# FT4232_MINI.net
KiCad netlist of a schematic drawn in Altium Designer
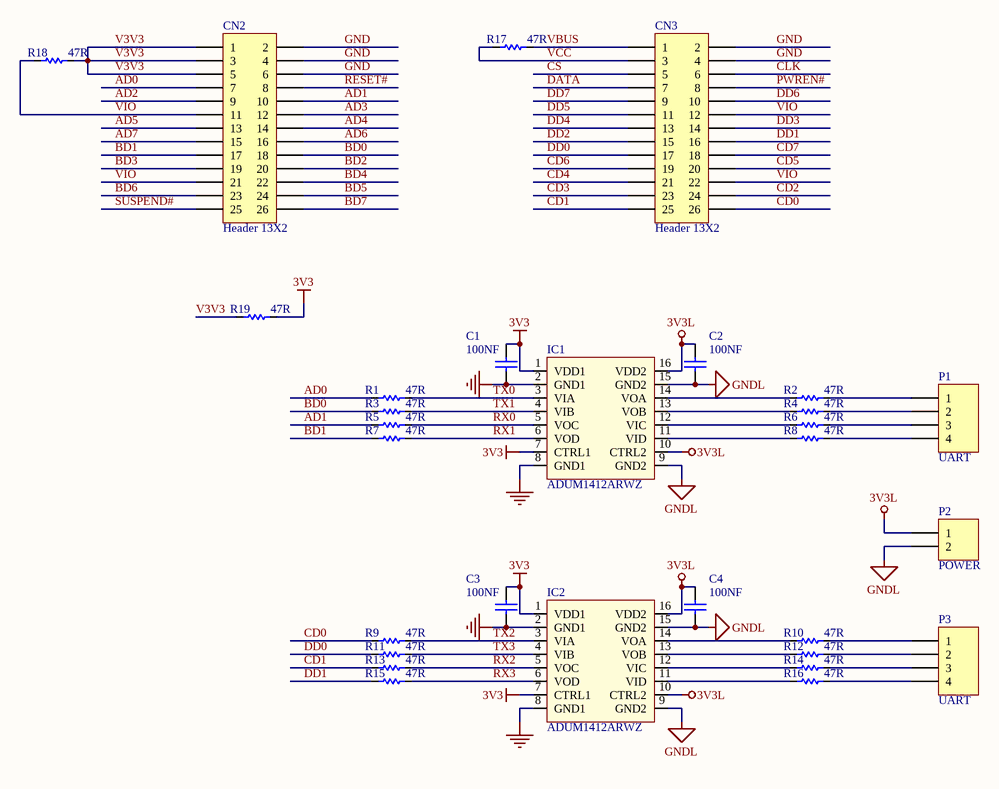
[diagram p0: FT4232_MINI.SchDoc]

(export (version "E")
  (design (tool "Eeschema 10.0.6"))
  (components
    (comp (ref "C1")
      (value "100NF")
      (footprint "CAPC1608X09N")
      (description "CAP CERAMIC 100NF 50VDC 10% SMD 0603   X7R")
      (libsource (lib "VIKO") (part "C_Nonpolar"))
    )
    (comp (ref "C2")
      (value "100NF")
      (footprint "CAPC1608X09N")
      (description "CAP CERAMIC 100NF 50VDC 10% SMD 0603   X7R")
      (libsource (lib "VIKO") (part "C_Nonpolar"))
    )
    (comp (ref "C3")
      (value "100NF")
      (footprint "CAPC1608X09N")
      (description "CAP CERAMIC 100NF 50VDC 10% SMD 0603   X7R")
      (libsource (lib "VIKO") (part "C_Nonpolar"))
    )
    (comp (ref "C4")
      (value "100NF")
      (footprint "CAPC1608X09N")
      (description "CAP CERAMIC 100NF 50VDC 10% SMD 0603   X7R")
      (libsource (lib "VIKO") (part "C_Nonpolar"))
    )
    (comp (ref "CN2")
      (value "Header 13X2")
      (footprint "Pin Header 2x13 TH Pitch 2.54mm")
      (description "Header, 13-Pin, Dual row")
      (fields (field (name "PUBLISHER") "Altium Limited"))
      (libsource (lib "Miscellaneous Connectors") (part "Header 13X2"))
    )
    (comp (ref "CN3")
      (value "Header 13X2")
      (footprint "Pin Header 2x13 TH Pitch 2.54mm")
      (description "Header, 13-Pin, Dual row")
      (fields (field (name "PUBLISHER") "Altium Limited"))
      (libsource (lib "Miscellaneous Connectors") (part "Header 13X2"))
    )
    (comp (ref "IC1")
      (value "ADUM1412ARWZ")
      (footprint "SOIC127P1030X265-16N")
      (description "IC DIGITAL ISOLATOR ADUM1412ARWZ 4 CH SMD SOIC16-W")
      (libsource (lib "VIKO") (part "IC-ADUM1412ARWZ"))
    )
    (comp (ref "IC2")
      (value "ADUM1412ARWZ")
      (footprint "SOIC127P1030X265-16N")
      (description "IC DIGITAL ISOLATOR ADUM1412ARWZ 4 CH SMD SOIC16-W")
      (libsource (lib "VIKO") (part "IC-ADUM1412ARWZ"))
    )
    (comp (ref "P1")
      (value "UART")
      (footprint "Klemens-3.81mm-4H")
      (description "Header, 4-Pin")
      (fields (field (name "PUBLISHER") "Altium Limited"))
      (libsource (lib "Miscellaneous Connectors") (part "Header 4"))
    )
    (comp (ref "P2")
      (value "POWER")
      (footprint "Klemens-3.81mm-2H")
      (description "Header, 2-Pin")
      (fields (field (name "PUBLISHER") "Altium Limited"))
      (libsource (lib "Miscellaneous Connectors") (part "Header 2"))
    )
    (comp (ref "P3")
      (value "UART")
      (footprint "Klemens-3.81mm-4H")
      (description "Header, 4-Pin")
      (fields (field (name "PUBLISHER") "Altium Limited"))
      (libsource (lib "Miscellaneous Connectors") (part "Header 4"))
    )
    (comp (ref "R1")
      (value "47R")
      (footprint "RESC1608X06N")
      (description "RES CARBON 47R 0.1W 1% 100ppm SMD 0603")
      (libsource (lib "VIKO") (part "R"))
    )
    (comp (ref "R2")
      (value "47R")
      (footprint "RESC1608X06N")
      (description "RES CARBON 47R 0.1W 1% 100ppm SMD 0603")
      (libsource (lib "VIKO") (part "R"))
    )
    (comp (ref "R3")
      (value "47R")
      (footprint "RESC1608X06N")
      (description "RES CARBON 47R 0.1W 1% 100ppm SMD 0603")
      (libsource (lib "VIKO") (part "R"))
    )
    (comp (ref "R4")
      (value "47R")
      (footprint "RESC1608X06N")
      (description "RES CARBON 47R 0.1W 1% 100ppm SMD 0603")
      (libsource (lib "VIKO") (part "R"))
    )
    (comp (ref "R5")
      (value "47R")
      (footprint "RESC1608X06N")
      (description "RES CARBON 47R 0.1W 1% 100ppm SMD 0603")
      (libsource (lib "VIKO") (part "R"))
    )
    (comp (ref "R6")
      (value "47R")
      (footprint "RESC1608X06N")
      (description "RES CARBON 47R 0.1W 1% 100ppm SMD 0603")
      (libsource (lib "VIKO") (part "R"))
    )
    (comp (ref "R7")
      (value "47R")
      (footprint "RESC1608X06N")
      (description "RES CARBON 47R 0.1W 1% 100ppm SMD 0603")
      (libsource (lib "VIKO") (part "R"))
    )
    (comp (ref "R8")
      (value "47R")
      (footprint "RESC1608X06N")
      (description "RES CARBON 47R 0.1W 1% 100ppm SMD 0603")
      (libsource (lib "VIKO") (part "R"))
    )
    (comp (ref "R9")
      (value "47R")
      (footprint "RESC1608X06N")
      (description "RES CARBON 47R 0.1W 1% 100ppm SMD 0603")
      (libsource (lib "VIKO") (part "R"))
    )
    (comp (ref "R10")
      (value "47R")
      (footprint "RESC1608X06N")
      (description "RES CARBON 47R 0.1W 1% 100ppm SMD 0603")
      (libsource (lib "VIKO") (part "R"))
    )
    (comp (ref "R11")
      (value "47R")
      (footprint "RESC1608X06N")
      (description "RES CARBON 47R 0.1W 1% 100ppm SMD 0603")
      (libsource (lib "VIKO") (part "R"))
    )
    (comp (ref "R12")
      (value "47R")
      (footprint "RESC1608X06N")
      (description "RES CARBON 47R 0.1W 1% 100ppm SMD 0603")
      (libsource (lib "VIKO") (part "R"))
    )
    (comp (ref "R13")
      (value "47R")
      (footprint "RESC1608X06N")
      (description "RES CARBON 47R 0.1W 1% 100ppm SMD 0603")
      (libsource (lib "VIKO") (part "R"))
    )
    (comp (ref "R14")
      (value "47R")
      (footprint "RESC1608X06N")
      (description "RES CARBON 47R 0.1W 1% 100ppm SMD 0603")
      (libsource (lib "VIKO") (part "R"))
    )
    (comp (ref "R15")
      (value "47R")
      (footprint "RESC1608X06N")
      (description "RES CARBON 47R 0.1W 1% 100ppm SMD 0603")
      (libsource (lib "VIKO") (part "R"))
    )
    (comp (ref "R16")
      (value "47R")
      (footprint "RESC1608X06N")
      (description "RES CARBON 47R 0.1W 1% 100ppm SMD 0603")
      (libsource (lib "VIKO") (part "R"))
    )
    (comp (ref "R17")
      (value "47R")
      (footprint "RESC1608X06N")
      (description "RES CARBON 47R 0.1W 1% 100ppm SMD 0603")
      (libsource (lib "VIKO") (part "R"))
    )
    (comp (ref "R18")
      (value "47R")
      (footprint "RESC1608X06N")
      (description "RES CARBON 47R 0.1W 1% 100ppm SMD 0603")
      (libsource (lib "VIKO") (part "R"))
    )
    (comp (ref "R19")
      (value "47R")
      (footprint "RESC1608X06N")
      (description "RES CARBON 47R 0.1W 1% 100ppm SMD 0603")
      (libsource (lib "VIKO") (part "R"))
    )
  )
  (nets
    (net (code "1") (name "/AD0") (class "Default")
      (node (ref "CN2") (pin "7") (pinfunction "7_7") (pintype "passive"))
      (node (ref "R1") (pin "1") (pinfunction "1_1") (pintype "passive"))
    )
    (net (code "2") (name "/AD1") (class "Default")
      (node (ref "CN2") (pin "10") (pinfunction "10_10") (pintype "passive"))
      (node (ref "R5") (pin "1") (pinfunction "1_1") (pintype "passive"))
    )
    (net (code "3") (name "/AD2") (class "Default")
      (node (ref "CN2") (pin "9") (pinfunction "9_9") (pintype "passive"))
    )
    (net (code "4") (name "/AD3") (class "Default")
      (node (ref "CN2") (pin "12") (pinfunction "12_12") (pintype "passive"))
    )
    (net (code "5") (name "/AD4") (class "Default")
      (node (ref "CN2") (pin "14") (pinfunction "14_14") (pintype "passive"))
    )
    (net (code "6") (name "/AD5") (class "Default")
      (node (ref "CN2") (pin "13") (pinfunction "13_13") (pintype "passive"))
    )
    (net (code "7") (name "/AD6") (class "Default")
      (node (ref "CN2") (pin "16") (pinfunction "16_16") (pintype "passive"))
    )
    (net (code "8") (name "/AD7") (class "Default")
      (node (ref "CN2") (pin "15") (pinfunction "15_15") (pintype "passive"))
    )
    (net (code "9") (name "/BD0") (class "Default")
      (node (ref "CN2") (pin "18") (pinfunction "18_18") (pintype "passive"))
      (node (ref "R3") (pin "1") (pinfunction "1_1") (pintype "passive"))
    )
    (net (code "10") (name "/BD1") (class "Default")
      (node (ref "CN2") (pin "17") (pinfunction "17_17") (pintype "passive"))
      (node (ref "R7") (pin "1") (pinfunction "1_1") (pintype "passive"))
    )
    (net (code "11") (name "/BD2") (class "Default")
      (node (ref "CN2") (pin "20") (pinfunction "20_20") (pintype "passive"))
    )
    (net (code "12") (name "/BD3") (class "Default")
      (node (ref "CN2") (pin "19") (pinfunction "19_19") (pintype "passive"))
    )
    (net (code "13") (name "/BD4") (class "Default")
      (node (ref "CN2") (pin "22") (pinfunction "22_22") (pintype "passive"))
    )
    (net (code "14") (name "/BD5") (class "Default")
      (node (ref "CN2") (pin "24") (pinfunction "24_24") (pintype "passive"))
    )
    (net (code "15") (name "/BD6") (class "Default")
      (node (ref "CN2") (pin "23") (pinfunction "23_23") (pintype "passive"))
    )
    (net (code "16") (name "/BD7") (class "Default")
      (node (ref "CN2") (pin "26") (pinfunction "26_26") (pintype "passive"))
    )
    (net (code "17") (name "/CD0") (class "Default")
      (node (ref "CN3") (pin "26") (pinfunction "26_26") (pintype "passive"))
      (node (ref "R9") (pin "1") (pinfunction "1_1") (pintype "passive"))
    )
    (net (code "18") (name "/CD1") (class "Default")
      (node (ref "CN3") (pin "25") (pinfunction "25_25") (pintype "passive"))
      (node (ref "R13") (pin "1") (pinfunction "1_1") (pintype "passive"))
    )
    (net (code "19") (name "/CD2") (class "Default")
      (node (ref "CN3") (pin "24") (pinfunction "24_24") (pintype "passive"))
    )
    (net (code "20") (name "/CD3") (class "Default")
      (node (ref "CN3") (pin "23") (pinfunction "23_23") (pintype "passive"))
    )
    (net (code "21") (name "/CD4") (class "Default")
      (node (ref "CN3") (pin "21") (pinfunction "21_21") (pintype "passive"))
    )
    (net (code "22") (name "/CD5") (class "Default")
      (node (ref "CN3") (pin "20") (pinfunction "20_20") (pintype "passive"))
    )
    (net (code "23") (name "/CD6") (class "Default")
      (node (ref "CN3") (pin "19") (pinfunction "19_19") (pintype "passive"))
    )
    (net (code "24") (name "/CD7") (class "Default")
      (node (ref "CN3") (pin "18") (pinfunction "18_18") (pintype "passive"))
    )
    (net (code "25") (name "/CLK") (class "Default")
      (node (ref "CN3") (pin "6") (pinfunction "6_6") (pintype "passive"))
    )
    (net (code "26") (name "/CS") (class "Default")
      (node (ref "CN3") (pin "5") (pinfunction "5_5") (pintype "passive"))
    )
    (net (code "27") (name "/DATA") (class "Default")
      (node (ref "CN3") (pin "7") (pinfunction "7_7") (pintype "passive"))
    )
    (net (code "28") (name "/DD0") (class "Default")
      (node (ref "CN3") (pin "17") (pinfunction "17_17") (pintype "passive"))
      (node (ref "R11") (pin "1") (pinfunction "1_1") (pintype "passive"))
    )
    (net (code "29") (name "/DD1") (class "Default")
      (node (ref "CN3") (pin "16") (pinfunction "16_16") (pintype "passive"))
      (node (ref "R15") (pin "1") (pinfunction "1_1") (pintype "passive"))
    )
    (net (code "30") (name "/DD2") (class "Default")
      (node (ref "CN3") (pin "15") (pinfunction "15_15") (pintype "passive"))
    )
    (net (code "31") (name "/DD3") (class "Default")
      (node (ref "CN3") (pin "14") (pinfunction "14_14") (pintype "passive"))
    )
    (net (code "32") (name "/DD4") (class "Default")
      (node (ref "CN3") (pin "13") (pinfunction "13_13") (pintype "passive"))
    )
    (net (code "33") (name "/DD5") (class "Default")
      (node (ref "CN3") (pin "11") (pinfunction "11_11") (pintype "passive"))
    )
    (net (code "34") (name "/DD6") (class "Default")
      (node (ref "CN3") (pin "10") (pinfunction "10_10") (pintype "passive"))
    )
    (net (code "35") (name "/DD7") (class "Default")
      (node (ref "CN3") (pin "9") (pinfunction "9_9") (pintype "passive"))
    )
    (net (code "36") (name "/PWREN#") (class "Default")
      (node (ref "CN3") (pin "8") (pinfunction "8_8") (pintype "passive"))
    )
    (net (code "37") (name "/RESET#") (class "Default")
      (node (ref "CN2") (pin "8") (pinfunction "8_8") (pintype "passive"))
    )
    (net (code "38") (name "/RX0") (class "Default")
      (node (ref "IC1") (pin "5") (pinfunction "VOC_5") (pintype "passive"))
      (node (ref "R5") (pin "2") (pinfunction "2_2") (pintype "passive"))
    )
    (net (code "39") (name "/RX1") (class "Default")
      (node (ref "IC1") (pin "6") (pinfunction "VOD_6") (pintype "passive"))
      (node (ref "R7") (pin "2") (pinfunction "2_2") (pintype "passive"))
    )
    (net (code "40") (name "/RX2") (class "Default")
      (node (ref "IC2") (pin "5") (pinfunction "VOC_5") (pintype "passive"))
      (node (ref "R13") (pin "2") (pinfunction "2_2") (pintype "passive"))
    )
    (net (code "41") (name "/RX3") (class "Default")
      (node (ref "IC2") (pin "6") (pinfunction "VOD_6") (pintype "passive"))
      (node (ref "R15") (pin "2") (pinfunction "2_2") (pintype "passive"))
    )
    (net (code "42") (name "/SUSPEND#") (class "Default")
      (node (ref "CN2") (pin "25") (pinfunction "25_25") (pintype "passive"))
    )
    (net (code "43") (name "/TX0") (class "Default")
      (node (ref "IC1") (pin "3") (pinfunction "VIA_3") (pintype "passive"))
      (node (ref "R1") (pin "2") (pinfunction "2_2") (pintype "passive"))
    )
    (net (code "44") (name "/TX1") (class "Default")
      (node (ref "IC1") (pin "4") (pinfunction "VIB_4") (pintype "passive"))
      (node (ref "R3") (pin "2") (pinfunction "2_2") (pintype "passive"))
    )
    (net (code "45") (name "/TX2") (class "Default")
      (node (ref "IC2") (pin "3") (pinfunction "VIA_3") (pintype "passive"))
      (node (ref "R9") (pin "2") (pinfunction "2_2") (pintype "passive"))
    )
    (net (code "46") (name "/TX3") (class "Default")
      (node (ref "IC2") (pin "4") (pinfunction "VIB_4") (pintype "passive"))
      (node (ref "R11") (pin "2") (pinfunction "2_2") (pintype "passive"))
    )
    (net (code "47") (name "/V3V3") (class "Default")
      (node (ref "CN2") (pin "1") (pinfunction "1_1") (pintype "passive"))
      (node (ref "CN2") (pin "3") (pinfunction "3_3") (pintype "passive"))
      (node (ref "CN2") (pin "5") (pinfunction "5_5") (pintype "passive"))
      (node (ref "R18") (pin "2") (pinfunction "2_2") (pintype "passive"))
      (node (ref "R19") (pin "1") (pinfunction "1_1") (pintype "passive"))
    )
    (net (code "48") (name "/VBUS") (class "Default")
      (node (ref "CN3") (pin "1") (pinfunction "1_1") (pintype "passive"))
      (node (ref "R17") (pin "2") (pinfunction "2_2") (pintype "passive"))
    )
    (net (code "49") (name "/VCC") (class "Default")
      (node (ref "CN3") (pin "3") (pinfunction "3_3") (pintype "passive"))
      (node (ref "R17") (pin "1") (pinfunction "1_1") (pintype "passive"))
    )
    (net (code "50") (name "/VIO") (class "Default")
      (node (ref "CN2") (pin "11") (pinfunction "11_11") (pintype "passive"))
      (node (ref "CN2") (pin "21") (pinfunction "21_21") (pintype "passive"))
      (node (ref "CN3") (pin "12") (pinfunction "12_12") (pintype "passive"))
      (node (ref "CN3") (pin "22") (pinfunction "22_22") (pintype "passive"))
      (node (ref "R18") (pin "1") (pinfunction "1_1") (pintype "passive"))
    )
    (net (code "51") (name "3V3") (class "Default")
      (node (ref "C1") (pin "2") (pinfunction "2_2") (pintype "passive"))
      (node (ref "C3") (pin "2") (pinfunction "2_2") (pintype "passive"))
      (node (ref "IC1") (pin "1") (pinfunction "VDD1_1") (pintype "passive"))
      (node (ref "IC1") (pin "7") (pinfunction "CTRL1_7") (pintype "passive"))
      (node (ref "IC2") (pin "1") (pinfunction "VDD1_1") (pintype "passive"))
      (node (ref "IC2") (pin "7") (pinfunction "CTRL1_7") (pintype "passive"))
      (node (ref "R19") (pin "2") (pinfunction "2_2") (pintype "passive"))
    )
    (net (code "52") (name "3V3L") (class "Default")
      (node (ref "C2") (pin "2") (pinfunction "2_2") (pintype "passive"))
      (node (ref "C4") (pin "2") (pinfunction "2_2") (pintype "passive"))
      (node (ref "IC1") (pin "10") (pinfunction "CTRL2_10") (pintype "passive"))
      (node (ref "IC1") (pin "16") (pinfunction "VDD2_16") (pintype "passive"))
      (node (ref "IC2") (pin "10") (pinfunction "CTRL2_10") (pintype "passive"))
      (node (ref "IC2") (pin "16") (pinfunction "VDD2_16") (pintype "passive"))
      (node (ref "P2") (pin "1") (pinfunction "1_1") (pintype "passive"))
    )
    (net (code "53") (name "GND") (class "Default")
      (node (ref "C1") (pin "1") (pinfunction "1_1") (pintype "passive"))
      (node (ref "C3") (pin "1") (pinfunction "1_1") (pintype "passive"))
      (node (ref "CN2") (pin "2") (pinfunction "2_2") (pintype "passive"))
      (node (ref "CN2") (pin "4") (pinfunction "4_4") (pintype "passive"))
      (node (ref "CN2") (pin "6") (pinfunction "6_6") (pintype "passive"))
      (node (ref "CN3") (pin "2") (pinfunction "2_2") (pintype "passive"))
      (node (ref "CN3") (pin "4") (pinfunction "4_4") (pintype "passive"))
      (node (ref "IC1") (pin "2") (pinfunction "GND1_2") (pintype "passive"))
      (node (ref "IC1") (pin "8") (pinfunction "GND1_8") (pintype "passive"))
      (node (ref "IC2") (pin "2") (pinfunction "GND1_2") (pintype "passive"))
      (node (ref "IC2") (pin "8") (pinfunction "GND1_8") (pintype "passive"))
    )
    (net (code "54") (name "GNDL") (class "Default")
      (node (ref "C2") (pin "1") (pinfunction "1_1") (pintype "passive"))
      (node (ref "C4") (pin "1") (pinfunction "1_1") (pintype "passive"))
      (node (ref "IC1") (pin "15") (pinfunction "GND2_15") (pintype "passive"))
      (node (ref "IC1") (pin "9") (pinfunction "GND2_9") (pintype "passive"))
      (node (ref "IC2") (pin "15") (pinfunction "GND2_15") (pintype "passive"))
      (node (ref "IC2") (pin "9") (pinfunction "GND2_9") (pintype "passive"))
      (node (ref "P2") (pin "2") (pinfunction "2_2") (pintype "passive"))
    )
    (net (code "55") (name "Net-(IC1-VIC)") (class "Default")
      (node (ref "IC1") (pin "12") (pinfunction "VIC_12") (pintype "passive"))
      (node (ref "R6") (pin "1") (pinfunction "1_1") (pintype "passive"))
    )
    (net (code "56") (name "Net-(IC1-VID)") (class "Default")
      (node (ref "IC1") (pin "11") (pinfunction "VID_11") (pintype "passive"))
      (node (ref "R8") (pin "1") (pinfunction "1_1") (pintype "passive"))
    )
    (net (code "57") (name "Net-(IC1-VOA)") (class "Default")
      (node (ref "IC1") (pin "14") (pinfunction "VOA_14") (pintype "passive"))
      (node (ref "R2") (pin "1") (pinfunction "1_1") (pintype "passive"))
    )
    (net (code "58") (name "Net-(IC1-VOB)") (class "Default")
      (node (ref "IC1") (pin "13") (pinfunction "VOB_13") (pintype "passive"))
      (node (ref "R4") (pin "1") (pinfunction "1_1") (pintype "passive"))
    )
    (net (code "59") (name "Net-(IC2-VIC)") (class "Default")
      (node (ref "IC2") (pin "12") (pinfunction "VIC_12") (pintype "passive"))
      (node (ref "R14") (pin "1") (pinfunction "1_1") (pintype "passive"))
    )
    (net (code "60") (name "Net-(IC2-VID)") (class "Default")
      (node (ref "IC2") (pin "11") (pinfunction "VID_11") (pintype "passive"))
      (node (ref "R16") (pin "1") (pinfunction "1_1") (pintype "passive"))
    )
    (net (code "61") (name "Net-(IC2-VOA)") (class "Default")
      (node (ref "IC2") (pin "14") (pinfunction "VOA_14") (pintype "passive"))
      (node (ref "R10") (pin "1") (pinfunction "1_1") (pintype "passive"))
    )
    (net (code "62") (name "Net-(IC2-VOB)") (class "Default")
      (node (ref "IC2") (pin "13") (pinfunction "VOB_13") (pintype "passive"))
      (node (ref "R12") (pin "1") (pinfunction "1_1") (pintype "passive"))
    )
    (net (code "63") (name "Net-(P1-Pad1)") (class "Default")
      (node (ref "P1") (pin "1") (pinfunction "1_1") (pintype "passive"))
      (node (ref "R2") (pin "2") (pinfunction "2_2") (pintype "passive"))
    )
    (net (code "64") (name "Net-(P1-Pad2)") (class "Default")
      (node (ref "P1") (pin "2") (pinfunction "2_2") (pintype "passive"))
      (node (ref "R4") (pin "2") (pinfunction "2_2") (pintype "passive"))
    )
    (net (code "65") (name "Net-(P1-Pad3)") (class "Default")
      (node (ref "P1") (pin "3") (pinfunction "3_3") (pintype "passive"))
      (node (ref "R6") (pin "2") (pinfunction "2_2") (pintype "passive"))
    )
    (net (code "66") (name "Net-(P1-Pad4)") (class "Default")
      (node (ref "P1") (pin "4") (pinfunction "4_4") (pintype "passive"))
      (node (ref "R8") (pin "2") (pinfunction "2_2") (pintype "passive"))
    )
    (net (code "67") (name "Net-(P3-Pad1)") (class "Default")
      (node (ref "P3") (pin "1") (pinfunction "1_1") (pintype "passive"))
      (node (ref "R10") (pin "2") (pinfunction "2_2") (pintype "passive"))
    )
    (net (code "68") (name "Net-(P3-Pad2)") (class "Default")
      (node (ref "P3") (pin "2") (pinfunction "2_2") (pintype "passive"))
      (node (ref "R12") (pin "2") (pinfunction "2_2") (pintype "passive"))
    )
    (net (code "69") (name "Net-(P3-Pad3)") (class "Default")
      (node (ref "P3") (pin "3") (pinfunction "3_3") (pintype "passive"))
      (node (ref "R14") (pin "2") (pinfunction "2_2") (pintype "passive"))
    )
    (net (code "70") (name "Net-(P3-Pad4)") (class "Default")
      (node (ref "P3") (pin "4") (pinfunction "4_4") (pintype "passive"))
      (node (ref "R16") (pin "2") (pinfunction "2_2") (pintype "passive"))
    )
  )
)
